# mapleCUx_large_052.net
KiCad netlist of a schematic drawn in EAGLE
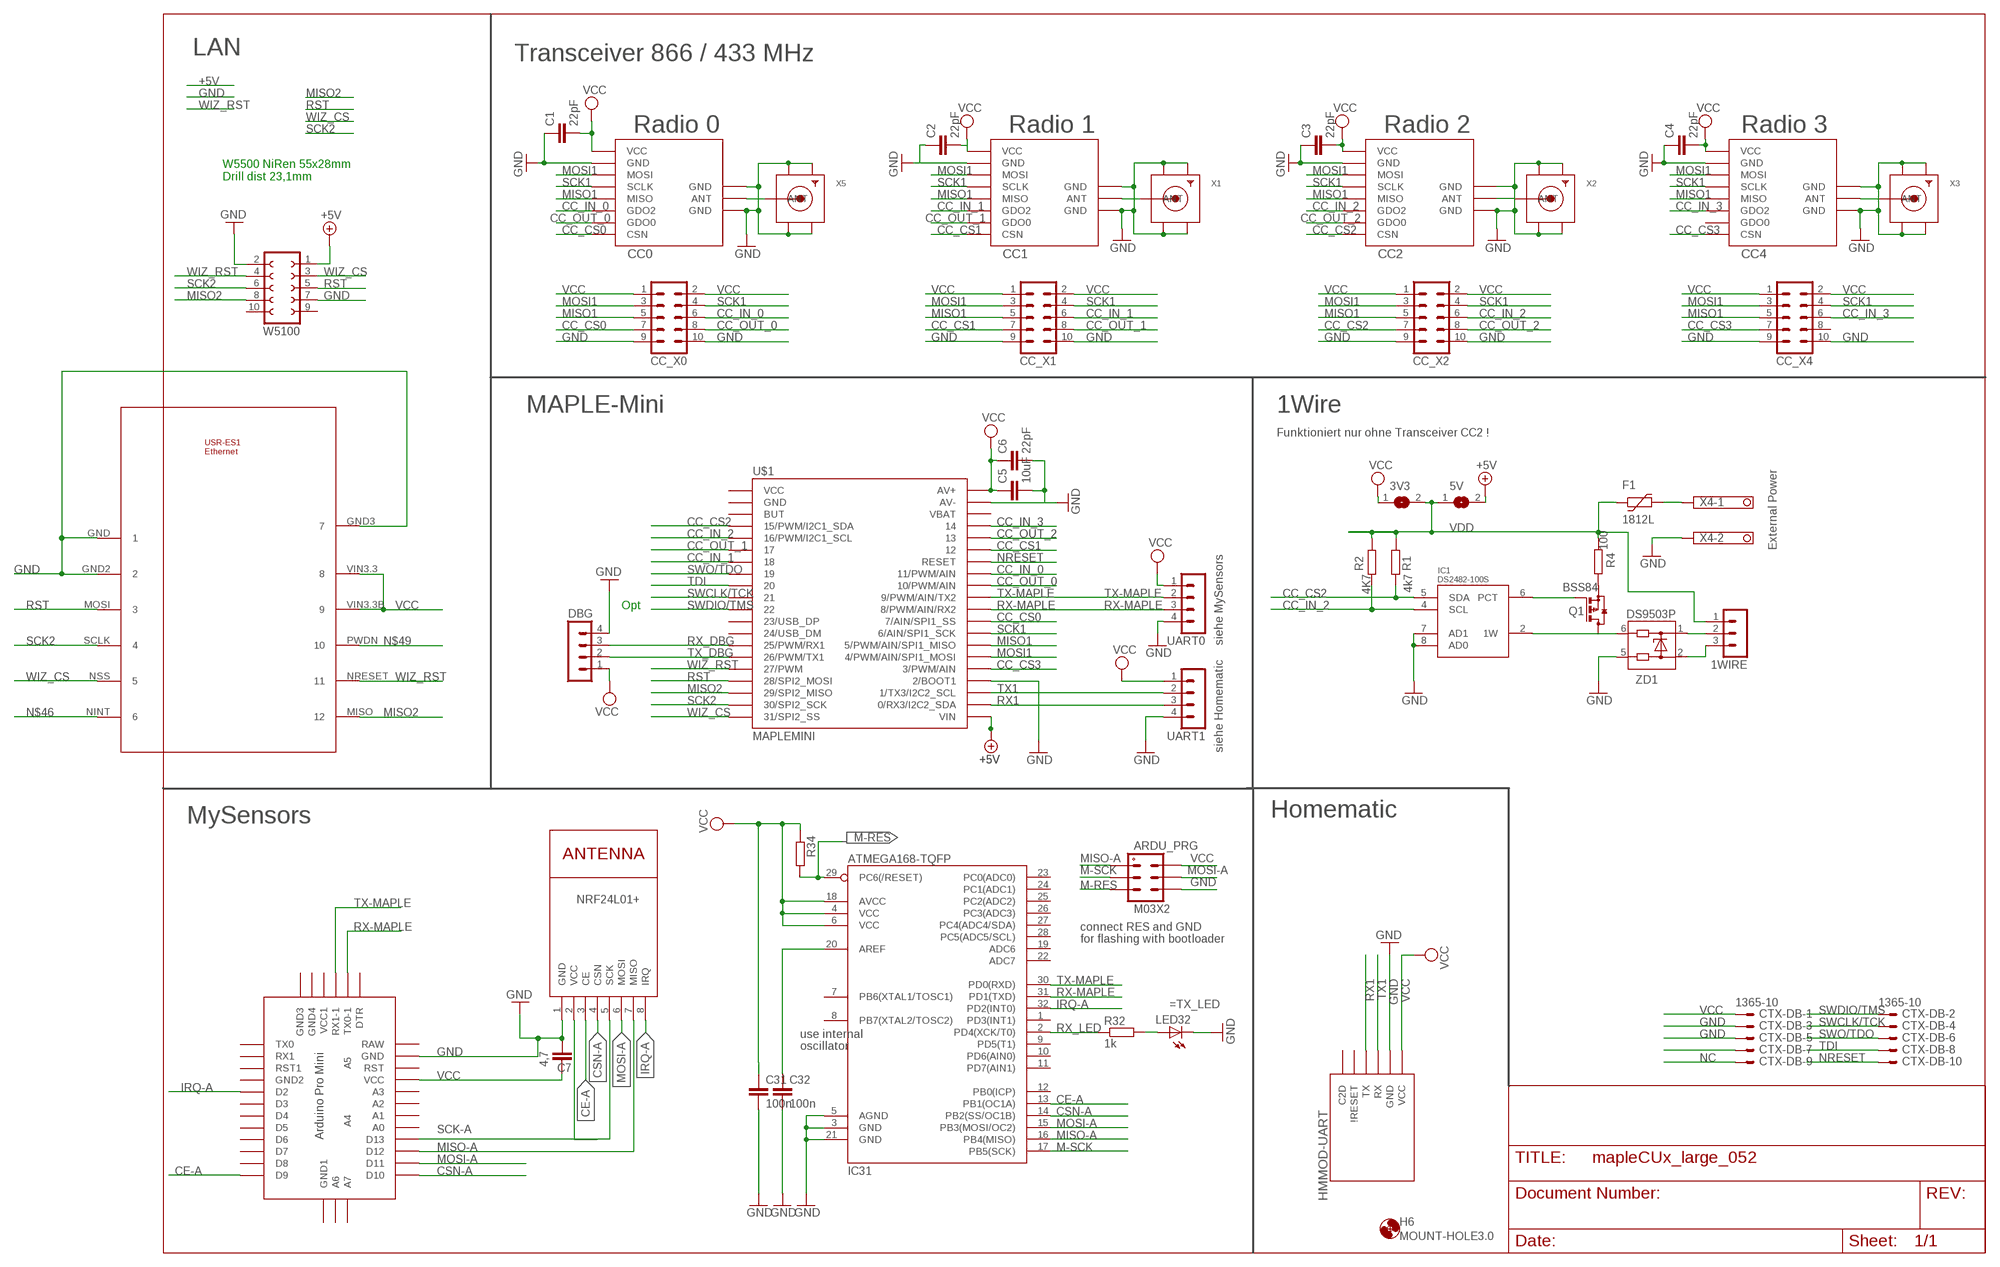
[diagram p0: schematic, sheet 1]

(export (version "E")
  (design (tool "Eeschema 10.0.6"))
  (components
    (comp (ref "1WIRE")
      (value "MA03-1")
      (footprint "eagle-import:MA03-1")
      (libsource (lib "eagle-import") (part "MA03-1"))
    )
    (comp (ref "3V3") (value "SJ") (footprint "eagle-import:SJ") (libsource (lib "eagle-import") (part "SJ")))
    (comp (ref "5V") (value "SJ") (footprint "eagle-import:SJ") (libsource (lib "eagle-import") (part "SJ")))
    (comp (ref "ARDU_PRG")
      (value "M03X2")
      (footprint "eagle-import:2X03-1.27MM_SMD")
      (libsource (lib "eagle-import") (part "M03X2"))
    )
    (comp (ref "C1")
      (value "22pF")
      (footprint "eagle-import:C0805")
      (libsource (lib "eagle-import") (part "C-EUC0805"))
    )
    (comp (ref "C2")
      (value "22pF")
      (footprint "eagle-import:C0805")
      (libsource (lib "eagle-import") (part "C-EUC0805"))
    )
    (comp (ref "C3")
      (value "22pF")
      (footprint "eagle-import:C0805")
      (libsource (lib "eagle-import") (part "C-EUC0805"))
    )
    (comp (ref "C4")
      (value "22pF")
      (footprint "eagle-import:C0805")
      (libsource (lib "eagle-import") (part "C-EUC0805"))
    )
    (comp (ref "C5")
      (value "10uF")
      (footprint "eagle-import:C1210")
      (libsource (lib "eagle-import") (part "C-EUC1210"))
    )
    (comp (ref "C6")
      (value "22pF")
      (footprint "eagle-import:C0805")
      (libsource (lib "eagle-import") (part "C-EUC0805"))
    )
    (comp (ref "C7")
      (value "4,7")
      (footprint "eagle-import:C1210")
      (libsource (lib "eagle-import") (part "C-EUC1210"))
    )
    (comp (ref "C31")
      (value "100n")
      (footprint "eagle-import:C0805")
      (libsource (lib "eagle-import") (part "C-EUC0805"))
    )
    (comp (ref "C32")
      (value "100n")
      (footprint "eagle-import:C0805")
      (libsource (lib "eagle-import") (part "C-EUC0805"))
    )
    (comp (ref "CC0")
      (value "CC1101_MODULE1SMD")
      (footprint "eagle-import:CC1101_MODULE1_SMD")
      (libsource (lib "eagle-import") (part "CC1101_MODULE1SMD"))
    )
    (comp (ref "CC1")
      (value "CC1101_MODULE1SMD")
      (footprint "eagle-import:CC1101_MODULE1_SMD")
      (libsource (lib "eagle-import") (part "CC1101_MODULE1SMD"))
    )
    (comp (ref "CC2")
      (value "CC1101_MODULE1SMD")
      (footprint "eagle-import:CC1101_MODULE1_SMD")
      (libsource (lib "eagle-import") (part "CC1101_MODULE1SMD"))
    )
    (comp (ref "CC4")
      (value "CC1101_MODULE1SMD")
      (footprint "eagle-import:CC1101_MODULE1_SMD")
      (libsource (lib "eagle-import") (part "CC1101_MODULE1SMD"))
    )
    (comp (ref "CC_X0")
      (value "MA05-2")
      (footprint "eagle-import:MA05-2")
      (libsource (lib "eagle-import") (part "MA05-2"))
    )
    (comp (ref "CC_X1")
      (value "MA05-2")
      (footprint "eagle-import:MA05-2")
      (libsource (lib "eagle-import") (part "MA05-2"))
    )
    (comp (ref "CC_X2")
      (value "MA05-2")
      (footprint "eagle-import:MA05-2")
      (libsource (lib "eagle-import") (part "MA05-2"))
    )
    (comp (ref "CC_X4")
      (value "MA05-2")
      (footprint "eagle-import:MA05-2")
      (libsource (lib "eagle-import") (part "MA05-2"))
    )
    (comp (ref "CTX-DB")
      (value "1365-10")
      (footprint "eagle-import:1365-10")
      (libsource (lib "eagle-import") (part "1365-10"))
    )
    (comp (ref "DBG")
      (value "MA04-1")
      (footprint "eagle-import:MA04-1")
      (libsource (lib "eagle-import") (part "MA04-1"))
    )
    (comp (ref "F1")
      (value "1812L")
      (footprint "eagle-import:1812L")
      (libsource (lib "eagle-import") (part "1812L"))
    )
    (comp (ref "H6")
      (value "MOUNT-HOLE3.0")
      (footprint "eagle-import:3,0")
      (libsource (lib "eagle-import") (part "MOUNT-HOLE3.0"))
    )
    (comp (ref "HMMOD-UART")
      (value "HM-MOD-UARTDIL")
      (footprint "eagle-import:HM-MOD-UART-DIL")
      (libsource (lib "eagle-import") (part "HM-MOD-UARTDIL"))
    )
    (comp (ref "IC1")
      (value "DS2482-100S")
      (footprint "eagle-import:SO08")
      (libsource (lib "eagle-import") (part "DS2482-100S"))
    )
    (comp (ref "IC31")
      (value "ATMEGA168-TQFP")
      (footprint "eagle-import:TQFP32-08")
      (libsource (lib "eagle-import") (part "ATMEGA168-TQFP"))
    )
    (comp (ref "LED32")
      (value "LEDCHIPLED_0805")
      (footprint "eagle-import:CHIPLED_0805")
      (libsource (lib "eagle-import") (part "LEDCHIPLED_0805"))
    )
    (comp (ref "NRF24L01+")
      (value "NRF24L01+")
      (footprint "eagle-import:WIRELESS-NRF24L01")
      (libsource (lib "eagle-import") (part "WIRELESS-NRF24L01"))
    )
    (comp (ref "Q1")
      (value "BSS84")
      (footprint "eagle-import:SOT23")
      (libsource (lib "eagle-import") (part "BSS84"))
    )
    (comp (ref "R1")
      (value "4k7")
      (footprint "eagle-import:R0805")
      (libsource (lib "eagle-import") (part "R-EU_R0805"))
    )
    (comp (ref "R2")
      (value "4K7")
      (footprint "eagle-import:R0805")
      (libsource (lib "eagle-import") (part "R-EU_R0805"))
    )
    (comp (ref "R4")
      (value "100")
      (footprint "eagle-import:R0805")
      (libsource (lib "eagle-import") (part "R-EU_R0805"))
    )
    (comp (ref "R32")
      (value "1k")
      (footprint "eagle-import:R0805")
      (libsource (lib "eagle-import") (part "R-EU_R0805"))
    )
    (comp (ref "R34")
      (value "R-EU_R0805")
      (footprint "eagle-import:R0805")
      (libsource (lib "eagle-import") (part "R-EU_R0805"))
    )
    (comp (ref "U$1")
      (value "MAPLEMINI")
      (footprint "eagle-import:20-DIP")
      (libsource (lib "eagle-import") (part "MAPLEMINI"))
    )
    (comp (ref "U$2")
      (value "ABK-PRO-MINI")
      (footprint "eagle-import:ABK-PRO-MINI")
      (libsource (lib "eagle-import") (part "ABK-PRO-MINI"))
    )
    (comp (ref "U$3")
      (value "USR-ES1")
      (footprint "eagle-import:USR-ES1")
      (libsource (lib "eagle-import") (part "USR-ES1"))
    )
    (comp (ref "UART0")
      (value "MA04-1")
      (footprint "eagle-import:MA04-1")
      (libsource (lib "eagle-import") (part "MA04-1"))
    )
    (comp (ref "UART1")
      (value "MA04-1")
      (footprint "eagle-import:MA04-1")
      (libsource (lib "eagle-import") (part "MA04-1"))
    )
    (comp (ref "W5100")
      (value "FE05-2")
      (footprint "eagle-import:FE05-2")
      (libsource (lib "eagle-import") (part "FE05-2"))
    )
    (comp (ref "X1")
      (value "SMACONNECTOR_EDGE_UFL")
      (footprint "eagle-import:SMA_EDGELAUNCH_UFL")
      (libsource (lib "eagle-import") (part "SMACONNECTOR_EDGE_UFL"))
    )
    (comp (ref "X2")
      (value "SMACONNECTOR_EDGE_UFL")
      (footprint "eagle-import:SMA_EDGELAUNCH_UFL")
      (libsource (lib "eagle-import") (part "SMACONNECTOR_EDGE_UFL"))
    )
    (comp (ref "X3")
      (value "SMACONNECTOR_EDGE_UFL")
      (footprint "eagle-import:SMA_EDGELAUNCH_UFL")
      (libsource (lib "eagle-import") (part "SMACONNECTOR_EDGE_UFL"))
    )
    (comp (ref "X4")
      (value "1751248")
      (footprint "eagle-import:1751248")
      (libsource (lib "eagle-import") (part "1751248"))
    )
    (comp (ref "X5")
      (value "SMACONNECTOR_EDGE_UFL")
      (footprint "eagle-import:SMA_EDGELAUNCH_UFL")
      (libsource (lib "eagle-import") (part "SMACONNECTOR_EDGE_UFL"))
    )
    (comp (ref "ZD1")
      (value "DS9503P")
      (footprint "eagle-import:TSOC6")
      (libsource (lib "eagle-import") (part "DS9503P"))
    )
  )
  (nets
    (net (code "1") (name "+5V") (class "Default")
      (node (ref "5V") (pin "2") (pinfunction "2_2") (pintype "passive"))
      (node (ref "U$1") (pin "21") (pinfunction "VIN_21") (pintype "bidirectional"))
      (node (ref "W5100") (pin "1") (pinfunction "1_1") (pintype "passive"))
    )
    (net (code "2") (name "/CC_CS0") (class "Default")
      (node (ref "CC0") (pin "CSN") (pinfunction "CSN_CSN") (pintype "bidirectional"))
      (node (ref "CC_X0") (pin "7") (pinfunction "7_7") (pintype "passive"))
      (node (ref "U$1") (pin "29") (pinfunction "7/AIN/SPI1_SS_29") (pintype "bidirectional"))
    )
    (net (code "3") (name "/CC_CS1") (class "Default")
      (node (ref "CC1") (pin "CSN") (pinfunction "CSN_CSN") (pintype "bidirectional"))
      (node (ref "CC_X1") (pin "7") (pinfunction "7_7") (pintype "passive"))
      (node (ref "U$1") (pin "35") (pinfunction "12_35") (pintype "bidirectional"))
    )
    (net (code "4") (name "/CC_CS2") (class "Default")
      (node (ref "CC2") (pin "CSN") (pinfunction "CSN_CSN") (pintype "bidirectional"))
      (node (ref "CC_X2") (pin "7") (pinfunction "7_7") (pintype "passive"))
      (node (ref "IC1") (pin "5") (pinfunction "SDA_5") (pintype "bidirectional"))
      (node (ref "R1") (pin "2") (pinfunction "2_2") (pintype "passive"))
      (node (ref "U$1") (pin "4") (pinfunction "15/PWM/I2C1_SDA_4") (pintype "bidirectional"))
    )
    (net (code "5") (name "/CC_CS3") (class "Default")
      (node (ref "CC4") (pin "CSN") (pinfunction "CSN_CSN") (pintype "bidirectional"))
      (node (ref "CC_X4") (pin "7") (pinfunction "7_7") (pintype "passive"))
      (node (ref "U$1") (pin "25") (pinfunction "3/PWM/AIN_25") (pintype "bidirectional"))
    )
    (net (code "6") (name "/CC_IN_0") (class "Default")
      (node (ref "CC0") (pin "GDO2") (pinfunction "GDO2_GDO2") (pintype "bidirectional"))
      (node (ref "CC_X0") (pin "6") (pinfunction "6_6") (pintype "passive"))
      (node (ref "U$1") (pin "33") (pinfunction "11/PWM/AIN_33") (pintype "bidirectional"))
    )
    (net (code "7") (name "/CC_IN_1") (class "Default")
      (node (ref "CC1") (pin "GDO2") (pinfunction "GDO2_GDO2") (pintype "bidirectional"))
      (node (ref "CC_X1") (pin "6") (pinfunction "6_6") (pintype "passive"))
      (node (ref "U$1") (pin "7") (pinfunction "18_7") (pintype "bidirectional"))
    )
    (net (code "8") (name "/CC_IN_2") (class "Default")
      (node (ref "CC2") (pin "GDO2") (pinfunction "GDO2_GDO2") (pintype "bidirectional"))
      (node (ref "CC_X2") (pin "6") (pinfunction "6_6") (pintype "passive"))
      (node (ref "IC1") (pin "4") (pinfunction "SCL_4") (pintype "input"))
      (node (ref "R2") (pin "2") (pinfunction "2_2") (pintype "passive"))
      (node (ref "U$1") (pin "5") (pinfunction "16/PWM/I2C1_SCL_5") (pintype "bidirectional"))
    )
    (net (code "9") (name "/CC_IN_3") (class "Default")
      (node (ref "CC4") (pin "GDO2") (pinfunction "GDO2_GDO2") (pintype "bidirectional"))
      (node (ref "CC_X4") (pin "6") (pinfunction "6_6") (pintype "passive"))
      (node (ref "U$1") (pin "37") (pinfunction "14_37") (pintype "bidirectional"))
    )
    (net (code "10") (name "/CC_OUT_0") (class "Default")
      (node (ref "CC0") (pin "GDO0") (pinfunction "GDO0_GDO0") (pintype "bidirectional"))
      (node (ref "CC_X0") (pin "8") (pinfunction "8_8") (pintype "passive"))
      (node (ref "U$1") (pin "32") (pinfunction "10/PWM/AIN_32") (pintype "bidirectional"))
    )
    (net (code "11") (name "/CC_OUT_1") (class "Default")
      (node (ref "CC1") (pin "GDO0") (pinfunction "GDO0_GDO0") (pintype "bidirectional"))
      (node (ref "CC_X1") (pin "8") (pinfunction "8_8") (pintype "passive"))
      (node (ref "U$1") (pin "6") (pinfunction "17_6") (pintype "bidirectional"))
    )
    (net (code "12") (name "/CC_OUT_2") (class "Default")
      (node (ref "CC2") (pin "GDO0") (pinfunction "GDO0_GDO0") (pintype "bidirectional"))
      (node (ref "CC_X2") (pin "8") (pinfunction "8_8") (pintype "passive"))
      (node (ref "U$1") (pin "36") (pinfunction "13_36") (pintype "bidirectional"))
    )
    (net (code "13") (name "/M-RES") (class "Default")
      (node (ref "ARDU_PRG") (pin "P$5") (pinfunction "5_P$5") (pintype "passive"))
      (node (ref "IC31") (pin "29") (pinfunction "PC6(/RESET)_29") (pintype "bidirectional"))
      (node (ref "R34") (pin "2") (pinfunction "2_2") (pintype "passive"))
    )
    (net (code "14") (name "/M-SCK") (class "Default")
      (node (ref "ARDU_PRG") (pin "P$3") (pinfunction "3_P$3") (pintype "passive"))
      (node (ref "IC31") (pin "17") (pinfunction "PB5(SCK)_17") (pintype "bidirectional"))
    )
    (net (code "15") (name "/MISO-A") (class "Default")
      (node (ref "ARDU_PRG") (pin "P$1") (pinfunction "1_P$1") (pintype "passive"))
      (node (ref "IC31") (pin "16") (pinfunction "PB4(MISO)_16") (pintype "bidirectional"))
      (node (ref "NRF24L01+") (pin "7") (pinfunction "MISO_7") (pintype "bidirectional"))
      (node (ref "U$2") (pin "D12") (pinfunction "D12_D12") (pintype "bidirectional"))
    )
    (net (code "16") (name "/MISO1") (class "Default")
      (node (ref "CC0") (pin "MISO") (pinfunction "MISO_MISO") (pintype "bidirectional"))
      (node (ref "CC1") (pin "MISO") (pinfunction "MISO_MISO") (pintype "bidirectional"))
      (node (ref "CC2") (pin "MISO") (pinfunction "MISO_MISO") (pintype "bidirectional"))
      (node (ref "CC4") (pin "MISO") (pinfunction "MISO_MISO") (pintype "bidirectional"))
      (node (ref "CC_X0") (pin "5") (pinfunction "5_5") (pintype "passive"))
      (node (ref "CC_X1") (pin "5") (pinfunction "5_5") (pintype "passive"))
      (node (ref "CC_X2") (pin "5") (pinfunction "5_5") (pintype "passive"))
      (node (ref "CC_X4") (pin "5") (pinfunction "5_5") (pintype "passive"))
      (node (ref "U$1") (pin "27") (pinfunction "5/PWM/AIN/SPI1_MISO_27") (pintype "bidirectional"))
    )
    (net (code "17") (name "/MISO2") (class "Default")
      (node (ref "U$1") (pin "18") (pinfunction "29/SPI2_MISO_18") (pintype "bidirectional"))
      (node (ref "U$3") (pin "MISO") (pinfunction "12_MISO") (pintype "bidirectional"))
      (node (ref "W5100") (pin "8") (pinfunction "8_8") (pintype "passive"))
    )
    (net (code "18") (name "/MOSI1") (class "Default")
      (node (ref "CC0") (pin "MOSI") (pinfunction "MOSI_MOSI") (pintype "bidirectional"))
      (node (ref "CC1") (pin "MOSI") (pinfunction "MOSI_MOSI") (pintype "bidirectional"))
      (node (ref "CC2") (pin "MOSI") (pinfunction "MOSI_MOSI") (pintype "bidirectional"))
      (node (ref "CC4") (pin "MOSI") (pinfunction "MOSI_MOSI") (pintype "bidirectional"))
      (node (ref "CC_X0") (pin "3") (pinfunction "3_3") (pintype "passive"))
      (node (ref "CC_X1") (pin "3") (pinfunction "3_3") (pintype "passive"))
      (node (ref "CC_X2") (pin "3") (pinfunction "3_3") (pintype "passive"))
      (node (ref "CC_X4") (pin "3") (pinfunction "3_3") (pintype "passive"))
      (node (ref "U$1") (pin "26") (pinfunction "4/PWM/AIN/SPI1_MOSI_26") (pintype "bidirectional"))
    )
    (net (code "19") (name "/N$46") (class "Default")
      (node (ref "U$3") (pin "NINT") (pinfunction "6_NINT") (pintype "bidirectional"))
    )
    (net (code "20") (name "/N$49") (class "Default")
      (node (ref "U$3") (pin "PWDN") (pinfunction "10_PWDN") (pintype "bidirectional"))
    )
    (net (code "21") (name "/NC") (class "Default")
      (node (ref "CTX-DB") (pin "9") (pinfunction "S_9") (pintype "passive"))
    )
    (net (code "22") (name "/NRESET") (class "Default")
      (node (ref "CTX-DB") (pin "10") (pinfunction "S_10") (pintype "passive"))
      (node (ref "U$1") (pin "34") (pinfunction "RESET_34") (pintype "bidirectional"))
    )
    (net (code "23") (name "/RST") (class "Default")
      (node (ref "U$1") (pin "17") (pinfunction "28/SPI2_MOSI_17") (pintype "bidirectional"))
      (node (ref "U$3") (pin "MOSI") (pinfunction "3_MOSI") (pintype "bidirectional"))
      (node (ref "W5100") (pin "5") (pinfunction "5_5") (pintype "passive"))
    )
    (net (code "24") (name "/RX-MAPLE") (class "Default")
      (node (ref "IC31") (pin "31") (pinfunction "PD1(TXD)_31") (pintype "bidirectional"))
      (node (ref "U$1") (pin "30") (pinfunction "8/PWM/AIN/RX2_30") (pintype "bidirectional"))
      (node (ref "U$2") (pin "TX0-1") (pinfunction "TX0-1_TX0-1") (pintype "bidirectional"))
      (node (ref "UART0") (pin "3") (pinfunction "3_3") (pintype "passive"))
    )
    (net (code "25") (name "/RX1") (class "Default")
      (node (ref "HMMOD-UART") (pin "5") (pinfunction "TX_5") (pintype "bidirectional"))
      (node (ref "U$1") (pin "22") (pinfunction "0/RX3/I2C2_SDA_22") (pintype "bidirectional"))
      (node (ref "UART1") (pin "3") (pinfunction "3_3") (pintype "passive"))
    )
    (net (code "26") (name "/RX_DBG") (class "Default")
      (node (ref "DBG") (pin "3") (pinfunction "3_3") (pintype "passive"))
      (node (ref "U$1") (pin "14") (pinfunction "25/PWM/RX1_14") (pintype "bidirectional"))
    )
    (net (code "27") (name "/RX_LED") (class "Default")
      (node (ref "IC31") (pin "2") (pinfunction "PD4(XCK/T0)_2") (pintype "bidirectional"))
      (node (ref "R32") (pin "1") (pinfunction "1_1") (pintype "passive"))
    )
    (net (code "28") (name "/SCK-A") (class "Default")
      (node (ref "NRF24L01+") (pin "5") (pinfunction "SCK_5") (pintype "bidirectional"))
      (node (ref "U$2") (pin "D13") (pinfunction "D13_D13") (pintype "bidirectional"))
    )
    (net (code "29") (name "/SCK1") (class "Default")
      (node (ref "CC0") (pin "SCLK") (pinfunction "SCLK_SCLK") (pintype "bidirectional"))
      (node (ref "CC1") (pin "SCLK") (pinfunction "SCLK_SCLK") (pintype "bidirectional"))
      (node (ref "CC2") (pin "SCLK") (pinfunction "SCLK_SCLK") (pintype "bidirectional"))
      (node (ref "CC4") (pin "SCLK") (pinfunction "SCLK_SCLK") (pintype "bidirectional"))
      (node (ref "CC_X0") (pin "4") (pinfunction "4_4") (pintype "passive"))
      (node (ref "CC_X1") (pin "4") (pinfunction "4_4") (pintype "passive"))
      (node (ref "CC_X2") (pin "4") (pinfunction "4_4") (pintype "passive"))
      (node (ref "CC_X4") (pin "4") (pinfunction "4_4") (pintype "passive"))
      (node (ref "U$1") (pin "28") (pinfunction "6/AIN/SPI1_SCK_28") (pintype "bidirectional"))
    )
    (net (code "30") (name "/SCK2") (class "Default")
      (node (ref "U$1") (pin "19") (pinfunction "30/SPI2_SCK_19") (pintype "bidirectional"))
      (node (ref "U$3") (pin "SCLK") (pinfunction "4_SCLK") (pintype "bidirectional"))
      (node (ref "W5100") (pin "6") (pinfunction "6_6") (pintype "passive"))
    )
    (net (code "31") (name "/SWCLK{slash}TCK") (class "Default")
      (node (ref "CTX-DB") (pin "4") (pinfunction "S_4") (pintype "passive"))
      (node (ref "U$1") (pin "10") (pinfunction "21_10") (pintype "bidirectional"))
    )
    (net (code "32") (name "/SWDIO{slash}TMS") (class "Default")
      (node (ref "CTX-DB") (pin "2") (pinfunction "S_2") (pintype "passive"))
      (node (ref "U$1") (pin "11") (pinfunction "22_11") (pintype "bidirectional"))
    )
    (net (code "33") (name "/SWO{slash}TDO") (class "Default")
      (node (ref "CTX-DB") (pin "6") (pinfunction "S_6") (pintype "passive"))
      (node (ref "U$1") (pin "8") (pinfunction "19_8") (pintype "bidirectional"))
    )
    (net (code "34") (name "/TDI") (class "Default")
      (node (ref "CTX-DB") (pin "8") (pinfunction "S_8") (pintype "passive"))
      (node (ref "U$1") (pin "9") (pinfunction "20_9") (pintype "bidirectional"))
    )
    (net (code "35") (name "/TX-MAPLE") (class "Default")
      (node (ref "IC31") (pin "30") (pinfunction "PD0(RXD)_30") (pintype "bidirectional"))
      (node (ref "U$1") (pin "31") (pinfunction "9/PWM/AIN/TX2_31") (pintype "bidirectional"))
      (node (ref "U$2") (pin "RX1-1") (pinfunction "RX1-1_RX1-1") (pintype "bidirectional"))
      (node (ref "UART0") (pin "2") (pinfunction "2_2") (pintype "passive"))
    )
    (net (code "36") (name "/TX1") (class "Default")
      (node (ref "HMMOD-UART") (pin "6") (pinfunction "RX_6") (pintype "bidirectional"))
      (node (ref "U$1") (pin "23") (pinfunction "1/TX3/I2C2_SCL_23") (pintype "bidirectional"))
      (node (ref "UART1") (pin "2") (pinfunction "2_2") (pintype "passive"))
    )
    (net (code "37") (name "/TX_DBG") (class "Default")
      (node (ref "DBG") (pin "2") (pinfunction "2_2") (pintype "passive"))
      (node (ref "U$1") (pin "15") (pinfunction "26/PWM/TX1_15") (pintype "bidirectional"))
    )
    (net (code "38") (name "/VDD") (class "Default")
      (node (ref "1WIRE") (pin "1") (pinfunction "1_1") (pintype "passive"))
      (node (ref "3V3") (pin "2") (pinfunction "2_2") (pintype "passive"))
      (node (ref "5V") (pin "1") (pinfunction "1_1") (pintype "passive"))
      (node (ref "F1") (pin "P$1") (pinfunction "1_P$1") (pintype "passive"))
      (node (ref "R1") (pin "1") (pinfunction "1_1") (pintype "passive"))
      (node (ref "R2") (pin "1") (pinfunction "1_1") (pintype "passive"))
      (node (ref "R4") (pin "2") (pinfunction "2_2") (pintype "passive"))
    )
    (net (code "39") (name "/WIZ_CS") (class "Default")
      (node (ref "U$1") (pin "20") (pinfunction "31/SPI2_SS_20") (pintype "bidirectional"))
      (node (ref "U$3") (pin "NSS") (pinfunction "5_NSS") (pintype "bidirectional"))
      (node (ref "W5100") (pin "3") (pinfunction "3_3") (pintype "passive"))
    )
    (net (code "40") (name "/WIZ_RST") (class "Default")
      (node (ref "U$1") (pin "16") (pinfunction "27/PWM_16") (pintype "bidirectional"))
      (node (ref "U$3") (pin "NRESET") (pinfunction "11_NRESET") (pintype "bidirectional"))
      (node (ref "W5100") (pin "4") (pinfunction "4_4") (pintype "passive"))
    )
    (net (code "41") (name "CE-A") (class "Default")
      (node (ref "IC31") (pin "13") (pinfunction "PB1(OC1A)_13") (pintype "bidirectional"))
      (node (ref "NRF24L01+") (pin "3") (pinfunction "CE_3") (pintype "bidirectional"))
      (node (ref "U$2") (pin "D9") (pinfunction "D9_D9") (pintype "bidirectional"))
    )
    (net (code "42") (name "CSN-A") (class "Default")
      (node (ref "IC31") (pin "14") (pinfunction "PB2(SS/OC1B)_14") (pintype "bidirectional"))
      (node (ref "NRF24L01+") (pin "4") (pinfunction "CSN_4") (pintype "bidirectional"))
      (node (ref "U$2") (pin "D10") (pinfunction "D10_D10") (pintype "bidirectional"))
    )
    (net (code "43") (name "GND") (class "Default")
      (node (ref "ARDU_PRG") (pin "P$6") (pinfunction "6_P$6") (pintype "passive"))
      (node (ref "C1") (pin "1") (pinfunction "1_1") (pintype "passive"))
      (node (ref "C2") (pin "1") (pinfunction "1_1") (pintype "passive"))
      (node (ref "C3") (pin "1") (pinfunction "1_1") (pintype "passive"))
      (node (ref "C31") (pin "2") (pinfunction "2_2") (pintype "passive"))
      (node (ref "C32") (pin "2") (pinfunction "2_2") (pintype "passive"))
      (node (ref "C4") (pin "1") (pinfunction "1_1") (pintype "passive"))
      (node (ref "C5") (pin "2") (pinfunction "2_2") (pintype "passive"))
      (node (ref "C6") (pin "2") (pinfunction "2_2") (pintype "passive"))
      (node (ref "C7") (pin "1") (pinfunction "1_1") (pintype "passive"))
      (node (ref "CC0") (pin "GND@0") (pinfunction "GND_GND@0") (pintype "power_in"))
      (node (ref "CC0") (pin "GND@1") (pinfunction "GND_GND@1") (pintype "power_in"))
      (node (ref "CC0") (pin "GND@2") (pinfunction "GND_GND@2") (pintype "power_in"))
      (node (ref "CC1") (pin "GND@0") (pinfunction "GND_GND@0") (pintype "power_in"))
      (node (ref "CC1") (pin "GND@1") (pinfunction "GND_GND@1") (pintype "power_in"))
      (node (ref "CC1") (pin "GND@2") (pinfunction "GND_GND@2") (pintype "power_in"))
      (node (ref "CC2") (pin "GND@0") (pinfunction "GND_GND@0") (pintype "power_in"))
      (node (ref "CC2") (pin "GND@1") (pinfunction "GND_GND@1") (pintype "power_in"))
      (node (ref "CC2") (pin "GND@2") (pinfunction "GND_GND@2") (pintype "power_in"))
      (node (ref "CC4") (pin "GND@0") (pinfunction "GND_GND@0") (pintype "power_in"))
      (node (ref "CC4") (pin "GND@1") (pinfunction "GND_GND@1") (pintype "power_in"))
      (node (ref "CC4") (pin "GND@2") (pinfunction "GND_GND@2") (pintype "power_in"))
      (node (ref "CC_X0") (pin "10") (pinfunction "10_10") (pintype "passive"))
      (node (ref "CC_X0") (pin "9") (pinfunction "9_9") (pintype "passive"))
      (node (ref "CC_X1") (pin "10") (pinfunction "10_10") (pintype "passive"))
      (node (ref "CC_X1") (pin "9") (pinfunction "9_9") (pintype "passive"))
      (node (ref "CC_X2") (pin "10") (pinfunction "10_10") (pintype "passive"))
      (node (ref "CC_X2") (pin "9") (pinfunction "9_9") (pintype "passive"))
      (node (ref "CC_X4") (pin "10") (pinfunction "10_10") (pintype "passive"))
      (node (ref "CC_X4") (pin "9") (pinfunction "9_9") (pintype "passive"))
      (node (ref "CTX-DB") (pin "3") (pinfunction "S_3") (pintype "passive"))
      (node (ref "CTX-DB") (pin "5") (pinfunction "S_5") (pintype "passive"))
      (node (ref "DBG") (pin "4") (pinfunction "4_4") (pintype "passive"))
      (node (ref "HMMOD-UART") (pin "2") (pinfunction "GND_2") (pintype "power_in"))
      (node (ref "IC1") (pin "7") (pinfunction "AD1_7") (pintype "input"))
      (node (ref "IC1") (pin "8") (pinfunction "AD0_8") (pintype "input"))
      (node (ref "IC31") (pin "21") (pinfunction "GND_21") (pintype "bidirectional"))
      (node (ref "IC31") (pin "3") (pinfunction "GND_3") (pintype "bidirectional"))
      (node (ref "IC31") (pin "5") (pinfunction "AGND_5") (pintype "bidirectional"))
      (node (ref "LED32") (pin "C") (pinfunction "C_C") (pintype "passive"))
      (node (ref "NRF24L01+") (pin "1") (pinfunction "GND_1") (pintype "power_in"))
      (node (ref "U$1") (pin "24") (pinfunction "2/BOOT1_24") (pintype "bidirectional"))
      (node (ref "U$1") (pin "39") (pinfunction "AV-_39") (pintype "bidirectional"))
      (node (ref "U$2") (pin "GND") (pinfunction "GND_GND") (pintype "bidirectional"))
      (node (ref "U$3") (pin "GND") (pinfunction "1_GND") (pintype "power_in"))
      (node (ref "U$3") (pin "GND2") (pinfunction "2_GND2") (pintype "power_in"))
      (node (ref "U$3") (pin "GND3") (pinfunction "7_GND3") (pintype "power_in"))
      (node (ref "UART0") (pin "4") (pinfunction "4_4") (pintype "passive"))
      (node (ref "UART1") (pin "4") (pinfunction "4_4") (pintype "passive"))
      (node (ref "W5100") (pin "2") (pinfunction "2_2") (pintype "passive"))
      (node (ref "W5100") (pin "7") (pinfunction "7_7") (pintype "passive"))
      (node (ref "X1") (pin "GND@1") (pinfunction "GND1_GND@1") (pintype "power_in"))
      (node (ref "X1") (pin "GND@2") (pinfunction "GND2_GND@2") (pintype "power_in"))
      (node (ref "X1") (pin "GND@3") (pinfunction "GND3_GND@3") (pintype "power_in"))
      (node (ref "X1") (pin "GND@4") (pinfunction "GND4_GND@4") (pintype "power_in"))
      (node (ref "X2") (pin "GND@1") (pinfunction "GND1_GND@1") (pintype "power_in"))
      (node (ref "X2") (pin "GND@2") (pinfunction "GND2_GND@2") (pintype "power_in"))
      (node (ref "X2") (pin "GND@3") (pinfunction "GND3_GND@3") (pintype "power_in"))
      (node (ref "X2") (pin "GND@4") (pinfunction "GND4_GND@4") (pintype "power_in"))
      (node (ref "X3") (pin "GND@1") (pinfunction "GND1_GND@1") (pintype "power_in"))
      (node (ref "X3") (pin "GND@2") (pinfunction "GND2_GND@2") (pintype "power_in"))
      (node (ref "X3") (pin "GND@3") (pinfunction "GND3_GND@3") (pintype "power_in"))
      (node (ref "X3") (pin "GND@4") (pinfunction "GND4_GND@4") (pintype "power_in"))
      (node (ref "X4") (pin "2") (pinfunction "K_2") (pintype "passive"))
      (node (ref "X5") (pin "GND@1") (pinfunction "GND1_GND@1") (pintype "power_in"))
      (node (ref "X5") (pin "GND@2") (pinfunction "GND2_GND@2") (pintype "power_in"))
      (node (ref "X5") (pin "GND@3") (pinfunction "GND3_GND@3") (pintype "power_in"))
      (node (ref "X5") (pin "GND@4") (pinfunction "GND4_GND@4") (pintype "power_in"))
      (node (ref "ZD1") (pin "5") (pinfunction "P$3_5") (pintype "passive"))
    )
    (net (code "44") (name "IRQ-A") (class "Default")
      (node (ref "IC31") (pin "32") (pinfunction "PD2(INT0)_32") (pintype "bidirectional"))
      (node (ref "NRF24L01+") (pin "8") (pinfunction "IRQ_8") (pintype "bidirectional"))
      (node (ref "U$2") (pin "D2") (pinfunction "D2_D2") (pintype "bidirectional"))
    )
    (net (code "45") (name "MOSI-A") (class "Default")
      (node (ref "ARDU_PRG") (pin "P$4") (pinfunction "4_P$4") (pintype "passive"))
      (node (ref "IC31") (pin "15") (pinfunction "PB3(MOSI/OC2)_15") (pintype "bidirectional"))
      (node (ref "NRF24L01+") (pin "6") (pinfunction "MOSI_6") (pintype "bidirectional"))
      (node (ref "U$2") (pin "D11") (pinfunction "D11_D11") (pintype "bidirectional"))
    )
    (net (code "46") (name "Net-(F1-2)") (class "Default")
      (node (ref "F1") (pin "P$2") (pinfunction "2_P$2") (pintype "passive"))
      (node (ref "X4") (pin "1") (pinfunction "K_1") (pintype "passive"))
    )
    (net (code "47") (name "Net-(IC1A-1W)") (class "Default")
      (node (ref "IC1") (pin "2") (pinfunction "1W_2") (pintype "open_collector"))
      (node (ref "Q1") (pin "3") (pinfunction "D_3") (pintype "passive"))
      (node (ref "ZD1") (pin "6") (pinfunction "P$4_6") (pintype "passive"))
    )
    (net (code "48") (name "Net-(IC1A-PCT)") (class "Default")
      (node (ref "IC1") (pin "6") (pinfunction "PCT_6") (pintype "output"))
      (node (ref "Q1") (pin "1") (pinfunction "G_1") (pintype "passive"))
    )
    (net (code "49") (name "Net-(IC31-AREF)") (class "Default")
      (node (ref "C32") (pin "1") (pinfunction "1_1") (pintype "passive"))
      (node (ref "IC31") (pin "20") (pinfunction "AREF_20") (pintype "bidirectional"))
    )
    (net (code "50") (name "Net-(LED32-PadA)") (class "Default")
      (node (ref "LED32") (pin "A") (pinfunction "A_A") (pintype "passive"))
      (node (ref "R32") (pin "2") (pinfunction "2_2") (pintype "passive"))
    )
    (net (code "51") (name "Net-(Q1-S)") (class "Default")
      (node (ref "Q1") (pin "2") (pinfunction "S_2") (pintype "passive"))
      (node (ref "R4") (pin "1") (pinfunction "1_1") (pintype "passive"))
    )
    (net (code "52") (name "Net-(X1-ANT)") (class "Default")
      (node (ref "CC1") (pin "ANT") (pinfunction "ANT_ANT") (pintype "output"))
      (node (ref "X1") (pin "P") (pinfunction "ANT_P") (pintype "bidirectional"))
    )
    (net (code "53") (name "Net-(X2-ANT)") (class "Default")
      (node (ref "CC2") (pin "ANT") (pinfunction "ANT_ANT") (pintype "output"))
      (node (ref "X2") (pin "P") (pinfunction "ANT_P") (pintype "bidirectional"))
    )
    (net (code "54") (name "Net-(X3-ANT)") (class "Default")
      (node (ref "CC4") (pin "ANT") (pinfunction "ANT_ANT") (pintype "output"))
      (node (ref "X3") (pin "P") (pinfunction "ANT_P") (pintype "bidirectional"))
    )
    (net (code "55") (name "Net-(X5-ANT)") (class "Default")
      (node (ref "CC0") (pin "ANT") (pinfunction "ANT_ANT") (pintype "output"))
      (node (ref "X5") (pin "P") (pinfunction "ANT_P") (pintype "bidirectional"))
    )
    (net (code "56") (name "Net-(ZD1-P$1)") (class "Default")
      (node (ref "1WIRE") (pin "2") (pinfunction "2_2") (pintype "passive"))
      (node (ref "ZD1") (pin "1") (pinfunction "P$1_1") (pintype "passive"))
    )
    (net (code "57") (name "Net-(ZD1-P$2)") (class "Default")
      (node (ref "1WIRE") (pin "3") (pinfunction "3_3") (pintype "passive"))
      (node (ref "ZD1") (pin "2") (pinfunction "P$2_2") (pintype "passive"))
    )
    (net (code "58") (name "VCC") (class "Default")
      (node (ref "3V3") (pin "1") (pinfunction "1_1") (pintype "passive"))
      (node (ref "ARDU_PRG") (pin "P$2") (pinfunction "2_P$2") (pintype "passive"))
      (node (ref "C1") (pin "2") (pinfunction "2_2") (pintype "passive"))
      (node (ref "C2") (pin "2") (pinfunction "2_2") (pintype "passive"))
      (node (ref "C3") (pin "2") (pinfunction "2_2") (pintype "passive"))
      (node (ref "C31") (pin "1") (pinfunction "1_1") (pintype "passive"))
      (node (ref "C4") (pin "2") (pinfunction "2_2") (pintype "passive"))
      (node (ref "C5") (pin "1") (pinfunction "1_1") (pintype "passive"))
      (node (ref "C6") (pin "1") (pinfunction "1_1") (pintype "passive"))
      (node (ref "C7") (pin "2") (pinfunction "2_2") (pintype "passive"))
      (node (ref "CC0") (pin "VCC") (pinfunction "VCC_VCC") (pintype "power_in"))
      (node (ref "CC1") (pin "VCC") (pinfunction "VCC_VCC") (pintype "power_in"))
      (node (ref "CC2") (pin "VCC") (pinfunction "VCC_VCC") (pintype "power_in"))
      (node (ref "CC4") (pin "VCC") (pinfunction "VCC_VCC") (pintype "power_in"))
      (node (ref "CC_X0") (pin "1") (pinfunction "1_1") (pintype "passive"))
      (node (ref "CC_X0") (pin "2") (pinfunction "2_2") (pintype "passive"))
      (node (ref "CC_X1") (pin "1") (pinfunction "1_1") (pintype "passive"))
      (node (ref "CC_X1") (pin "2") (pinfunction "2_2") (pintype "passive"))
      (node (ref "CC_X2") (pin "1") (pinfunction "1_1") (pintype "passive"))
      (node (ref "CC_X2") (pin "2") (pinfunction "2_2") (pintype "passive"))
      (node (ref "CC_X4") (pin "1") (pinfunction "1_1") (pintype "passive"))
      (node (ref "CC_X4") (pin "2") (pinfunction "2_2") (pintype "passive"))
      (node (ref "CTX-DB") (pin "1") (pinfunction "S_1") (pintype "passive"))
      (node (ref "DBG") (pin "1") (pinfunction "1_1") (pintype "passive"))
      (node (ref "HMMOD-UART") (pin "1") (pinfunction "VCC_1") (pintype "power_in"))
      (node (ref "IC31") (pin "18") (pinfunction "AVCC_18") (pintype "bidirectional"))
      (node (ref "IC31") (pin "4") (pinfunction "VCC_4") (pintype "bidirectional"))
      (node (ref "IC31") (pin "6") (pinfunction "VCC_6") (pintype "bidirectional"))
      (node (ref "NRF24L01+") (pin "2") (pinfunction "VCC_2") (pintype "power_in"))
      (node (ref "R34") (pin "1") (pinfunction "1_1") (pintype "passive"))
      (node (ref "U$1") (pin "40") (pinfunction "AV+_40") (pintype "bidirectional"))
      (node (ref "U$2") (pin "VCC") (pinfunction "VCC_VCC") (pintype "bidirectional"))
      (node (ref "U$3") (pin "VIN3.3") (pinfunction "8_VIN3.3") (pintype "power_in"))
      (node (ref "U$3") (pin "VIN3.3B") (pinfunction "9_VIN3.3B") (pintype "bidirectional"))
      (node (ref "UART0") (pin "1") (pinfunction "1_1") (pintype "passive"))
      (node (ref "UART1") (pin "1") (pinfunction "1_1") (pintype "passive"))
    )
    (net (code "59") (name "unconnected-(CC4-PadGDO0)") (class "Default")
      (node (ref "CC4") (pin "GDO0") (pinfunction "GDO0_GDO0") (pintype "bidirectional"))
    )
    (net (code "60") (name "unconnected-(CC_X4-Pad8)") (class "Default")
      (node (ref "CC_X4") (pin "8") (pinfunction "8_8") (pintype "passive"))
    )
    (net (code "61") (name "unconnected-(CTX-DBH-S-Pad7)") (class "Default")
      (node (ref "CTX-DB") (pin "7") (pinfunction "S_7") (pintype "passive"))
    )
    (net (code "62") (name "unconnected-(HMMOD-UART-C2D-Pad3)") (class "Default")
      (node (ref "HMMOD-UART") (pin "3") (pinfunction "C2D_3") (pintype "bidirectional"))
    )
    (net (code "63") (name "unconnected-(HMMOD-UART-\\~{RESET}-Pad4)") (class "Default")
      (node (ref "HMMOD-UART") (pin "4") (pinfunction "\\~{RESET}_4") (pintype "bidirectional"))
    )
    (net (code "64") (name "unconnected-(IC31-ADC6-Pad19)") (class "Default")
      (node (ref "IC31") (pin "19") (pinfunction "ADC6_19") (pintype "bidirectional"))
    )
    (net (code "65") (name "unconnected-(IC31-ADC7-Pad22)") (class "Default")
      (node (ref "IC31") (pin "22") (pinfunction "ADC7_22") (pintype "bidirectional"))
    )
    (net (code "66") (name "unconnected-(IC31-PB0(ICP)-Pad12)") (class "Default")
      (node (ref "IC31") (pin "12") (pinfunction "PB0(ICP)_12") (pintype "bidirectional"))
    )
    (net (code "67") (name "unconnected-(IC31-PB6(XTAL1{slash}TOSC1)-Pad7)") (class "Default")
      (node (ref "IC31") (pin "7") (pinfunction "PB6(XTAL1/TOSC1)_7") (pintype "bidirectional"))
    )
    (net (code "68") (name "unconnected-(IC31-PB7(XTAL2{slash}TOSC2)-Pad8)") (class "Default")
      (node (ref "IC31") (pin "8") (pinfunction "PB7(XTAL2/TOSC2)_8") (pintype "bidirectional"))
    )
    (net (code "69") (name "unconnected-(IC31-PC0(ADC0)-Pad23)") (class "Default")
      (node (ref "IC31") (pin "23") (pinfunction "PC0(ADC0)_23") (pintype "bidirectional"))
    )
    (net (code "70") (name "unconnected-(IC31-PC1(ADC1)-Pad24)") (class "Default")
      (node (ref "IC31") (pin "24") (pinfunction "PC1(ADC1)_24") (pintype "bidirectional"))
    )
    (net (code "71") (name "unconnected-(IC31-PC2(ADC2)-Pad25)") (class "Default")
      (node (ref "IC31") (pin "25") (pinfunction "PC2(ADC2)_25") (pintype "bidirectional"))
    )
    (net (code "72") (name "unconnected-(IC31-PC3(ADC3)-Pad26)") (class "Default")
      (node (ref "IC31") (pin "26") (pinfunction "PC3(ADC3)_26") (pintype "bidirectional"))
    )
    (net (code "73") (name "unconnected-(IC31-PC4(ADC4{slash}SDA)-Pad27)") (class "Default")
      (node (ref "IC31") (pin "27") (pinfunction "PC4(ADC4/SDA)_27") (pintype "bidirectional"))
    )
    (net (code "74") (name "unconnected-(IC31-PC5(ADC5{slash}SCL)-Pad28)") (class "Default")
      (node (ref "IC31") (pin "28") (pinfunction "PC5(ADC5/SCL)_28") (pintype "bidirectional"))
    )
    (net (code "75") (name "unconnected-(IC31-PD3(INT1)-Pad1)") (class "Default")
      (node (ref "IC31") (pin "1") (pinfunction "PD3(INT1)_1") (pintype "bidirectional"))
    )
    (net (code "76") (name "unconnected-(IC31-PD5(T1)-Pad9)") (class "Default")
      (node (ref "IC31") (pin "9") (pinfunction "PD5(T1)_9") (pintype "bidirectional"))
    )
    (net (code "77") (name "unconnected-(IC31-PD6(AIN0)-Pad10)") (class "Default")
      (node (ref "IC31") (pin "10") (pinfunction "PD6(AIN0)_10") (pintype "bidirectional"))
    )
    (net (code "78") (name "unconnected-(IC31-PD7(AIN1)-Pad11)") (class "Default")
      (node (ref "IC31") (pin "11") (pinfunction "PD7(AIN1)_11") (pintype "bidirectional"))
    )
    (net (code "79") (name "unconnected-(U$1-23{slash}USB_DP-Pad12)") (class "Default")
      (node (ref "U$1") (pin "12") (pinfunction "23/USB_DP_12") (pintype "bidirectional"))
    )
    (net (code "80") (name "unconnected-(U$1-24{slash}USB_DM-Pad13)") (class "Default")
      (node (ref "U$1") (pin "13") (pinfunction "24/USB_DM_13") (pintype "bidirectional"))
    )
    (net (code "81") (name "unconnected-(U$1-BUT-Pad3)") (class "Default")
      (node (ref "U$1") (pin "3") (pinfunction "BUT_3") (pintype "bidirectional"))
    )
    (net (code "82") (name "unconnected-(U$1-GND-Pad2)") (class "Default")
      (node (ref "U$1") (pin "2") (pinfunction "GND_2") (pintype "bidirectional"))
    )
    (net (code "83") (name "unconnected-(U$1-VBAT-Pad38)") (class "Default")
      (node (ref "U$1") (pin "38") (pinfunction "VBAT_38") (pintype "bidirectional"))
    )
    (net (code "84") (name "unconnected-(U$1-VCC-Pad1)") (class "Default")
      (node (ref "U$1") (pin "1") (pinfunction "VCC_1") (pintype "bidirectional"))
    )
    (net (code "85") (name "unconnected-(U$2-GND1-PadGND4)") (class "Default")
      (node (ref "U$2") (pin "GND4") (pinfunction "GND1_GND4") (pintype "bidirectional"))
    )
    (net (code "86") (name "unconnected-(U$2-GND2-PadGND1)") (class "Default")
      (node (ref "U$2") (pin "GND1") (pinfunction "GND2_GND1") (pintype "bidirectional"))
    )
    (net (code "87") (name "unconnected-(U$2-GND3-PadGND2)") (class "Default")
      (node (ref "U$2") (pin "GND2") (pinfunction "GND3_GND2") (pintype "bidirectional"))
    )
    (net (code "88") (name "unconnected-(U$2-GND4-PadGND3)") (class "Default")
      (node (ref "U$2") (pin "GND3") (pinfunction "GND4_GND3") (pintype "bidirectional"))
    )
    (net (code "89") (name "unconnected-(U$2-PadA0)") (class "Default")
      (node (ref "U$2") (pin "A0") (pinfunction "A0_A0") (pintype "bidirectional"))
    )
    (net (code "90") (name "unconnected-(U$2-PadA1)") (class "Default")
      (node (ref "U$2") (pin "A1") (pinfunction "A1_A1") (pintype "bidirectional"))
    )
    (net (code "91") (name "unconnected-(U$2-PadA2)") (class "Default")
      (node (ref "U$2") (pin "A2") (pinfunction "A2_A2") (pintype "bidirectional"))
    )
    (net (code "92") (name "unconnected-(U$2-PadA3)") (class "Default")
      (node (ref "U$2") (pin "A3") (pinfunction "A3_A3") (pintype "bidirectional"))
    )
    (net (code "93") (name "unconnected-(U$2-PadA4)") (class "Default")
      (node (ref "U$2") (pin "A4") (pinfunction "A4_A4") (pintype "bidirectional"))
    )
    (net (code "94") (name "unconnected-(U$2-PadA5)") (class "Default")
      (node (ref "U$2") (pin "A5") (pinfunction "A5_A5") (pintype "bidirectional"))
    )
    (net (code "95") (name "unconnected-(U$2-PadA6)") (class "Default")
      (node (ref "U$2") (pin "A6") (pinfunction "A6_A6") (pintype "bidirectional"))
    )
    (net (code "96") (name "unconnected-(U$2-PadA7)") (class "Default")
      (node (ref "U$2") (pin "A7") (pinfunction "A7_A7") (pintype "bidirectional"))
    )
    (net (code "97") (name "unconnected-(U$2-PadD3)") (class "Default")
      (node (ref "U$2") (pin "D3") (pinfunction "D3_D3") (pintype "bidirectional"))
    )
    (net (code "98") (name "unconnected-(U$2-PadD4)") (class "Default")
      (node (ref "U$2") (pin "D4") (pinfunction "D4_D4") (pintype "bidirectional"))
    )
    (net (code "99") (name "unconnected-(U$2-PadD5)") (class "Default")
      (node (ref "U$2") (pin "D5") (pinfunction "D5_D5") (pintype "bidirectional"))
    )
    (net (code "100") (name "unconnected-(U$2-PadD6)") (class "Default")
      (node (ref "U$2") (pin "D6") (pinfunction "D6_D6") (pintype "bidirectional"))
    )
    (net (code "101") (name "unconnected-(U$2-PadD7)") (class "Default")
      (node (ref "U$2") (pin "D7") (pinfunction "D7_D7") (pintype "bidirectional"))
    )
    (net (code "102") (name "unconnected-(U$2-PadD8)") (class "Default")
      (node (ref "U$2") (pin "D8") (pinfunction "D8_D8") (pintype "bidirectional"))
    )
    (net (code "103") (name "unconnected-(U$2-PadDTR)") (class "Default")
      (node (ref "U$2") (pin "DTR") (pinfunction "DTR_DTR") (pintype "bidirectional"))
    )
    (net (code "104") (name "unconnected-(U$2-PadRAW)") (class "Default")
      (node (ref "U$2") (pin "RAW") (pinfunction "RAW_RAW") (pintype "bidirectional"))
    )
    (net (code "105") (name "unconnected-(U$2-PadRST)") (class "Default")
      (node (ref "U$2") (pin "RST") (pinfunction "RST_RST") (pintype "bidirectional"))
    )
    (net (code "106") (name "unconnected-(U$2-PadRST1)") (class "Default")
      (node (ref "U$2") (pin "RST1") (pinfunction "RST1_RST1") (pintype "bidirectional"))
    )
    (net (code "107") (name "unconnected-(U$2-PadRX1)") (class "Default")
      (node (ref "U$2") (pin "RX1") (pinfunction "RX1_RX1") (pintype "bidirectional"))
    )
    (net (code "108") (name "unconnected-(U$2-PadTX0)") (class "Default")
      (node (ref "U$2") (pin "TX0") (pinfunction "TX0_TX0") (pintype "bidirectional"))
    )
    (net (code "109") (name "unconnected-(U$2-PadVCC1)") (class "Default")
      (node (ref "U$2") (pin "VCC1") (pinfunction "VCC1_VCC1") (pintype "bidirectional"))
    )
    (net (code "110") (name "unconnected-(W5100-Pad9)") (class "Default")
      (node (ref "W5100") (pin "9") (pinfunction "9_9") (pintype "passive"))
    )
    (net (code "111") (name "unconnected-(W5100-Pad10)") (class "Default")
      (node (ref "W5100") (pin "10") (pinfunction "10_10") (pintype "passive"))
    )
  )
)
